# Switches.net
KiCad netlist of a schematic drawn in Altium Designer
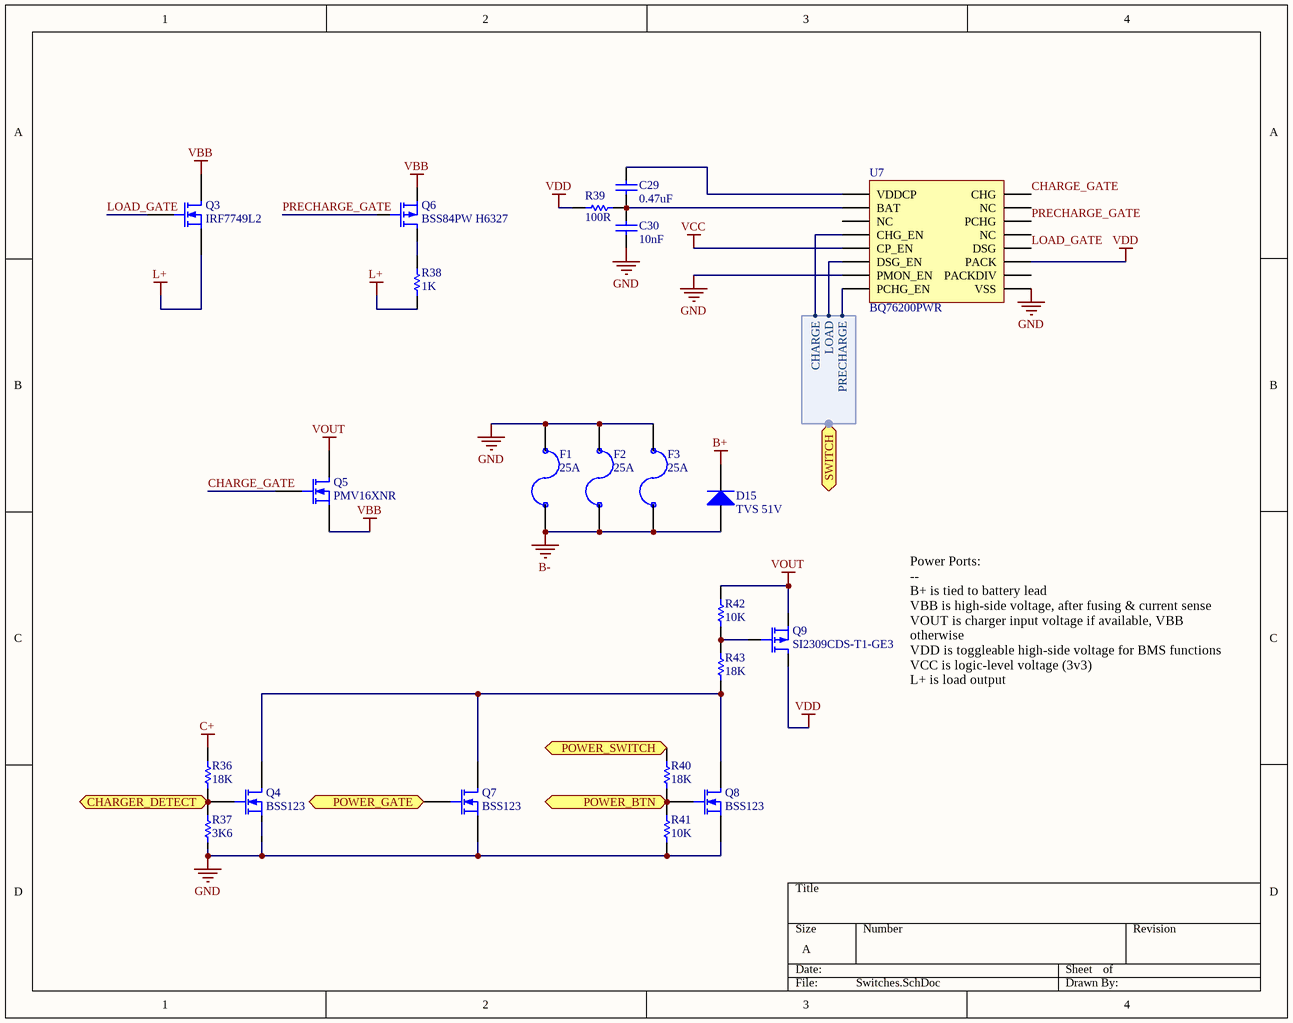
[diagram p0: Switches.SchDoc]

(export (version "E")
  (design (tool "Eeschema 10.0.6"))
  (components
    (comp (ref "C29")
      (value "0.47uF")
      (footprint "C0603[1608X92]")
      (description "0.47uF 50V 10% 0603 (1608 Metric)")
      (fields (field (name "TOLERANCE") "10%") (field (name "PARTNUMBER") "GRM188R61H474KA12D"))
      (libsource (lib "Capacitors") (part "CAP_0.47uF_50V_0603_10%"))
    )
    (comp (ref "C30")
      (value "10nF")
      (footprint "C0402[1005X55]")
      (description "10nF 50V 10% 0402 (1005 Metric)")
      (fields (field (name "TOLERANCE") "10%") (field (name "PARTNUMBER") "GCM155R71H103KA55D"))
      (libsource (lib "Capacitors") (part "CAP_10nF_50V_0402_10%"))
    )
    (comp (ref "D15")
      (value "TVS 51V")
      (footprint "VISH-DO-214AC-2_N")
      (fields
        (field (name "PARTNUMBER") "SMAJ51A-E3/61")
        (field (name "MANUFACTURER") "Vishay Semiconductor")
      )
      (libsource (lib "Altium Content Vault") (part "CMP-0548-00253-1"))
    )
    (comp (ref "F1")
      (value "FUSE 1206")
      (footprint "1206_FUSE")
      (description "Surface Mount Fuses UST 1206 FUSE 25A F")
      (fields
        (field (name "PARTNUMBER") "3413.0332.22")
        (field (name "MANUFACTURER") "Schurter")
        (field (name "CURRENT") "25A")
      )
      (libsource (lib "Components") (part "FUSE 1206"))
    )
    (comp (ref "F2")
      (value "FUSE 1206")
      (footprint "1206_FUSE")
      (description "Surface Mount Fuses UST 1206 FUSE 25A F")
      (fields
        (field (name "PARTNUMBER") "3413.0332.22")
        (field (name "MANUFACTURER") "Schurter")
        (field (name "CURRENT") "25A")
      )
      (libsource (lib "Components") (part "FUSE 1206"))
    )
    (comp (ref "F3")
      (value "FUSE 1206")
      (footprint "1206_FUSE")
      (description "Surface Mount Fuses UST 1206 FUSE 25A F")
      (fields
        (field (name "PARTNUMBER") "3413.0332.22")
        (field (name "MANUFACTURER") "Schurter")
        (field (name "CURRENT") "25A")
      )
      (libsource (lib "Components") (part "FUSE 1206"))
    )
    (comp (ref "Q3")
      (value "IRF7749L2")
      (footprint "DIRECTFET-9")
      (description "N-Channel MOSFET")
      (fields
        (field (name "PARTNUMBER") "IRF7749L2TRPBF")
        (field (name "MANUFACTURER") "Infineon Technologies")
      )
      (libsource (lib "MOSFETs") (part "IRF7749L2"))
    )
    (comp (ref "Q4")
      (value "BSS123")
      (footprint "SOT323-3")
      (description "N-Channel MOSFET")
      (fields (field (name "PARTNUMBER") "BSS123WQ-7-F") (field (name "MANUFACTURER") "Diodes Incorporated"))
      (libsource (lib "MOSFETs") (part "BSS123WQ-7-F"))
    )
    (comp (ref "Q5")
      (value "PMV16XNR")
      (footprint "SOT23-3")
      (description "N-Channel MOSFET")
      (fields (field (name "MANUFACTURER") "NXP"))
      (libsource (lib "MOSFETs") (part "PMV16XNR"))
    )
    (comp (ref "Q6")
      (value "BSS84PW H6327")
      (footprint "SOT323-3")
      (description "P-Channel MOSFET")
      (fields (field (name "MANUFACTURER") "Infineon"))
      (libsource (lib "MOSFETs") (part "BSS84PW H6327"))
    )
    (comp (ref "Q7")
      (value "BSS123")
      (footprint "SOT323-3")
      (description "N-Channel MOSFET")
      (fields (field (name "PARTNUMBER") "BSS123WQ-7-F") (field (name "MANUFACTURER") "Diodes Incorporated"))
      (libsource (lib "MOSFETs") (part "BSS123WQ-7-F"))
    )
    (comp (ref "Q8")
      (value "BSS123")
      (footprint "SOT323-3")
      (description "N-Channel MOSFET")
      (fields (field (name "PARTNUMBER") "BSS123WQ-7-F") (field (name "MANUFACTURER") "Diodes Incorporated"))
      (libsource (lib "MOSFETs") (part "BSS123WQ-7-F"))
    )
    (comp (ref "Q9")
      (value "SI2309CDS-T1-GE3")
      (footprint "SOT23-3")
      (description "P-Channel MOSFET")
      (fields (field (name "MANUFACTURER") "Vishay"))
      (libsource (lib "MOSFETs") (part "SI2309CDS-T1-GE3"))
    )
    (comp (ref "R36")
      (value "18K")
      (footprint "R0402[1005]")
      (description "18K 0.063W 1% 0402 (1005 Metric)")
      (fields (field (name "POWER") "0.063W") (field (name "TOLERANCE") "1%"))
      (libsource (lib "Resistors") (part "RES_18K_0402_1%"))
    )
    (comp (ref "R37")
      (value "3K6")
      (footprint "R0402[1005]")
      (description "3K6 0.063W 1% 0402 (1005 Metric)")
      (fields (field (name "TOLERANCE") "1%") (field (name "POWER") "0.063W"))
      (libsource (lib "Resistors") (part "RES_3K6_0402_1%"))
    )
    (comp (ref "R38")
      (value "1K")
      (footprint "R0805[2012]")
      (description "1K 0.5W 1% 0805 (2012 Metric)")
      (fields (field (name "TOLERANCE") "1%") (field (name "POWER") "0.5W"))
      (libsource (lib "Resistors") (part "RES_1K_0805_1%"))
    )
    (comp (ref "R39")
      (value "100R")
      (footprint "R0402[1005]")
      (description "100R 0.063W 1% 0402 (1005 Metric)")
      (fields (field (name "POWER") "0.063W") (field (name "TOLERANCE") "1%"))
      (libsource (lib "Resistors") (part "RES_100R_0402_1%"))
    )
    (comp (ref "R40")
      (value "18K")
      (footprint "R0402[1005]")
      (description "18K 0.063W 1% 0402 (1005 Metric)")
      (fields (field (name "TOLERANCE") "1%") (field (name "POWER") "0.063W"))
      (libsource (lib "Resistors") (part "RES_18K_0402_1%"))
    )
    (comp (ref "R41")
      (value "10K")
      (footprint "R0402[1005]")
      (description "10K 0.063W 1% 0402 (1005 Metric)")
      (fields (field (name "POWER") "0.063W") (field (name "TOLERANCE") "1%"))
      (libsource (lib "Resistors") (part "RES_10K_0402_1%"))
    )
    (comp (ref "R42")
      (value "10K")
      (footprint "R0402[1005]")
      (description "10K 0.063W 1% 0402 (1005 Metric)")
      (fields (field (name "TOLERANCE") "1%") (field (name "POWER") "0.063W"))
      (libsource (lib "Resistors") (part "RES_10K_0402_1%"))
    )
    (comp (ref "R43")
      (value "18K")
      (footprint "R0402[1005]")
      (description "18K 0.063W 1% 0402 (1005 Metric)")
      (fields (field (name "POWER") "0.063W") (field (name "TOLERANCE") "1%"))
      (libsource (lib "Resistors") (part "RES_18K_0402_1%"))
    )
    (comp (ref "U7")
      (value "BQ76200PWR")
      (footprint "TSSOP-16")
      (description "Battery Management Fast high side NCH drive")
      (fields (field (name "MANUFACTURER") "Texas Instruments"))
      (libsource (lib "ICs") (part "BQ76200PWR"))
    )
  )
  (nets
    (net (code "2") (name "/CHARGE") (class "Default")
      (node (ref "U7") (pin "4") (pinfunction "CHG_EN_4") (pintype "passive"))
    )
    (net (code "3") (name "/CHARGER_DETECT") (class "Default")
      (node (ref "Q4") (pin "1") (pinfunction "G_1") (pintype "passive"))
      (node (ref "R36") (pin "1") (pinfunction "1_1") (pintype "passive"))
      (node (ref "R37") (pin "2") (pinfunction "2_2") (pintype "passive"))
    )
    (net (code "4") (name "/CHARGE_GATE") (class "Default")
      (node (ref "Q5") (pin "1") (pinfunction "G_1") (pintype "passive"))
      (node (ref "U7") (pin "16") (pinfunction "CHG_16") (pintype "passive"))
    )
    (net (code "5") (name "/LOAD") (class "Default")
      (node (ref "U7") (pin "6") (pinfunction "DSG_EN_6") (pintype "passive"))
    )
    (net (code "6") (name "/LOAD_GATE") (class "Default")
      (node (ref "Q3") (pin "1") (pinfunction "G_1") (pintype "passive"))
      (node (ref "U7") (pin "12") (pinfunction "DSG_12") (pintype "passive"))
    )
    (net (code "7") (name "/POWER_BTN") (class "Default")
      (node (ref "Q8") (pin "1") (pinfunction "G_1") (pintype "passive"))
      (node (ref "R40") (pin "1") (pinfunction "1_1") (pintype "passive"))
      (node (ref "R41") (pin "2") (pinfunction "2_2") (pintype "passive"))
    )
    (net (code "8") (name "/POWER_GATE") (class "Default")
      (node (ref "Q7") (pin "1") (pinfunction "G_1") (pintype "passive"))
    )
    (net (code "9") (name "/POWER_SWITCH") (class "Default")
      (node (ref "R40") (pin "2") (pinfunction "2_2") (pintype "passive"))
    )
    (net (code "10") (name "/PRECHARGE") (class "Default")
      (node (ref "U7") (pin "8") (pinfunction "PCHG_EN_8") (pintype "passive"))
    )
    (net (code "11") (name "/PRECHARGE_GATE") (class "Default")
      (node (ref "Q6") (pin "1") (pinfunction "G_1") (pintype "passive"))
      (node (ref "U7") (pin "14") (pinfunction "PCHG_14") (pintype "passive"))
    )
    (net (code "13") (name "B+") (class "Default")
      (node (ref "D15") (pin "1") (pinfunction "K_1") (pintype "passive"))
    )
    (net (code "14") (name "B-") (class "Default")
      (node (ref "D15") (pin "2") (pinfunction "A_2") (pintype "passive"))
      (node (ref "F1") (pin "2") (pinfunction "2_2") (pintype "passive"))
      (node (ref "F2") (pin "2") (pinfunction "2_2") (pintype "passive"))
      (node (ref "F3") (pin "2") (pinfunction "2_2") (pintype "passive"))
    )
    (net (code "15") (name "C+") (class "Default")
      (node (ref "R36") (pin "2") (pinfunction "2_2") (pintype "passive"))
    )
    (net (code "16") (name "GND") (class "Default")
      (node (ref "C30") (pin "1") (pinfunction "1_1") (pintype "passive"))
      (node (ref "F1") (pin "1") (pinfunction "1_1") (pintype "passive"))
      (node (ref "F2") (pin "1") (pinfunction "1_1") (pintype "passive"))
      (node (ref "F3") (pin "1") (pinfunction "1_1") (pintype "passive"))
      (node (ref "Q4") (pin "2") (pinfunction "S_2") (pintype "passive"))
      (node (ref "Q7") (pin "2") (pinfunction "S_2") (pintype "passive"))
      (node (ref "Q8") (pin "2") (pinfunction "S_2") (pintype "passive"))
      (node (ref "R37") (pin "1") (pinfunction "1_1") (pintype "passive"))
      (node (ref "R41") (pin "1") (pinfunction "1_1") (pintype "passive"))
      (node (ref "U7") (pin "7") (pinfunction "PMON_EN_7") (pintype "passive"))
      (node (ref "U7") (pin "9") (pinfunction "VSS_9") (pintype "passive"))
    )
    (net (code "17") (name "L+") (class "Default")
      (node (ref "Q3") (pin "2") (pinfunction "S_2") (pintype "passive"))
      (node (ref "R38") (pin "1") (pinfunction "1_1") (pintype "passive"))
    )
    (net (code "18") (name "Net-(Q4-D)") (class "Default")
      (node (ref "Q4") (pin "3") (pinfunction "D_3") (pintype "passive"))
      (node (ref "Q7") (pin "3") (pinfunction "D_3") (pintype "passive"))
      (node (ref "Q8") (pin "3") (pinfunction "D_3") (pintype "passive"))
      (node (ref "R43") (pin "1") (pinfunction "1_1") (pintype "passive"))
    )
    (net (code "19") (name "Net-(Q6-D)") (class "Default")
      (node (ref "Q6") (pin "3") (pinfunction "D_3") (pintype "passive"))
      (node (ref "R38") (pin "2") (pinfunction "2_2") (pintype "passive"))
    )
    (net (code "20") (name "Net-(Q9-G)") (class "Default")
      (node (ref "Q9") (pin "1") (pinfunction "G_1") (pintype "passive"))
      (node (ref "R42") (pin "1") (pinfunction "1_1") (pintype "passive"))
      (node (ref "R43") (pin "2") (pinfunction "2_2") (pintype "passive"))
    )
    (net (code "21") (name "Net-(U7-BAT)") (class "Default")
      (node (ref "C29") (pin "1") (pinfunction "1_1") (pintype "passive"))
      (node (ref "C30") (pin "2") (pinfunction "2_2") (pintype "passive"))
      (node (ref "R39") (pin "2") (pinfunction "2_2") (pintype "passive"))
      (node (ref "U7") (pin "2") (pinfunction "BAT_2") (pintype "passive"))
    )
    (net (code "22") (name "Net-(U7-VDDCP)") (class "Default")
      (node (ref "C29") (pin "2") (pinfunction "2_2") (pintype "passive"))
      (node (ref "U7") (pin "1") (pinfunction "VDDCP_1") (pintype "passive"))
    )
    (net (code "23") (name "VBB") (class "Default")
      (node (ref "Q3") (pin "3") (pinfunction "D_3") (pintype "passive"))
      (node (ref "Q5") (pin "2") (pinfunction "S_2") (pintype "passive"))
      (node (ref "Q6") (pin "2") (pinfunction "S_2") (pintype "passive"))
    )
    (net (code "24") (name "VCC") (class "Default")
      (node (ref "U7") (pin "5") (pinfunction "CP_EN_5") (pintype "passive"))
    )
    (net (code "25") (name "VDD") (class "Default")
      (node (ref "Q9") (pin "2") (pinfunction "D_2") (pintype "passive"))
      (node (ref "R39") (pin "1") (pinfunction "1_1") (pintype "passive"))
      (node (ref "U7") (pin "11") (pinfunction "PACK_11") (pintype "passive"))
    )
    (net (code "26") (name "VOUT") (class "Default")
      (node (ref "Q5") (pin "3") (pinfunction "D_3") (pintype "passive"))
      (node (ref "Q9") (pin "3") (pinfunction "S_3") (pintype "passive"))
      (node (ref "R42") (pin "2") (pinfunction "2_2") (pintype "passive"))
    )
    (net (code "27") (name "unconnected-(U7-NC-Pad3)") (class "Default")
      (node (ref "U7") (pin "3") (pinfunction "NC_3") (pintype "passive"))
    )
    (net (code "28") (name "unconnected-(U7-NC-Pad13)") (class "Default")
      (node (ref "U7") (pin "13") (pinfunction "NC_13") (pintype "passive"))
    )
    (net (code "29") (name "unconnected-(U7-NC-Pad15)") (class "Default")
      (node (ref "U7") (pin "15") (pinfunction "NC_15") (pintype "passive"))
    )
    (net (code "30") (name "unconnected-(U7-PACKDIV-Pad10)") (class "Default")
      (node (ref "U7") (pin "10") (pinfunction "PACKDIV_10") (pintype "passive"))
    )
  )
)
